# Polarshield_v2_6.net
KiCad netlist of a schematic drawn in EAGLE
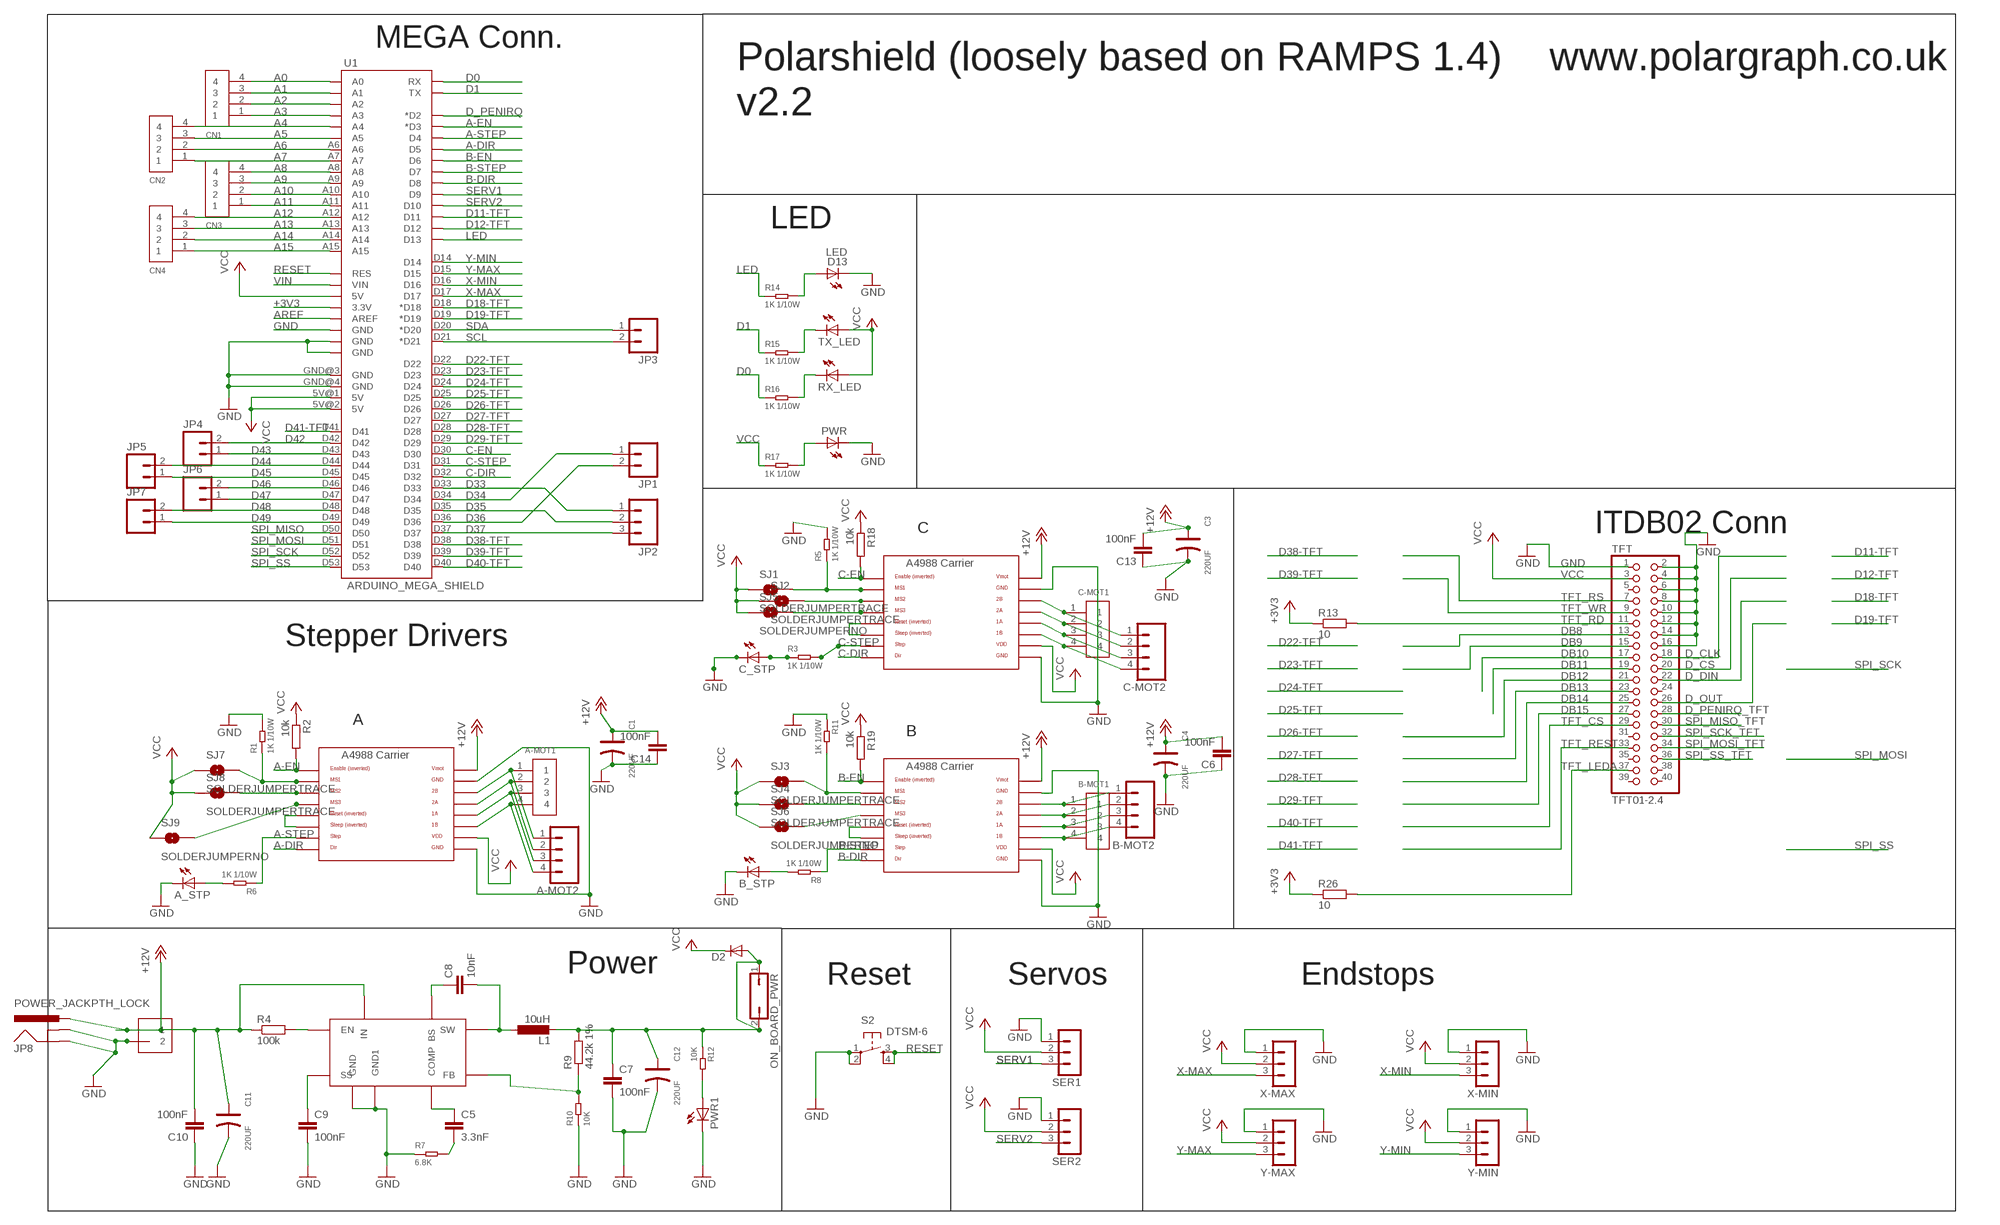
[diagram p0: schematic, sheet 1, part 1 of 2]
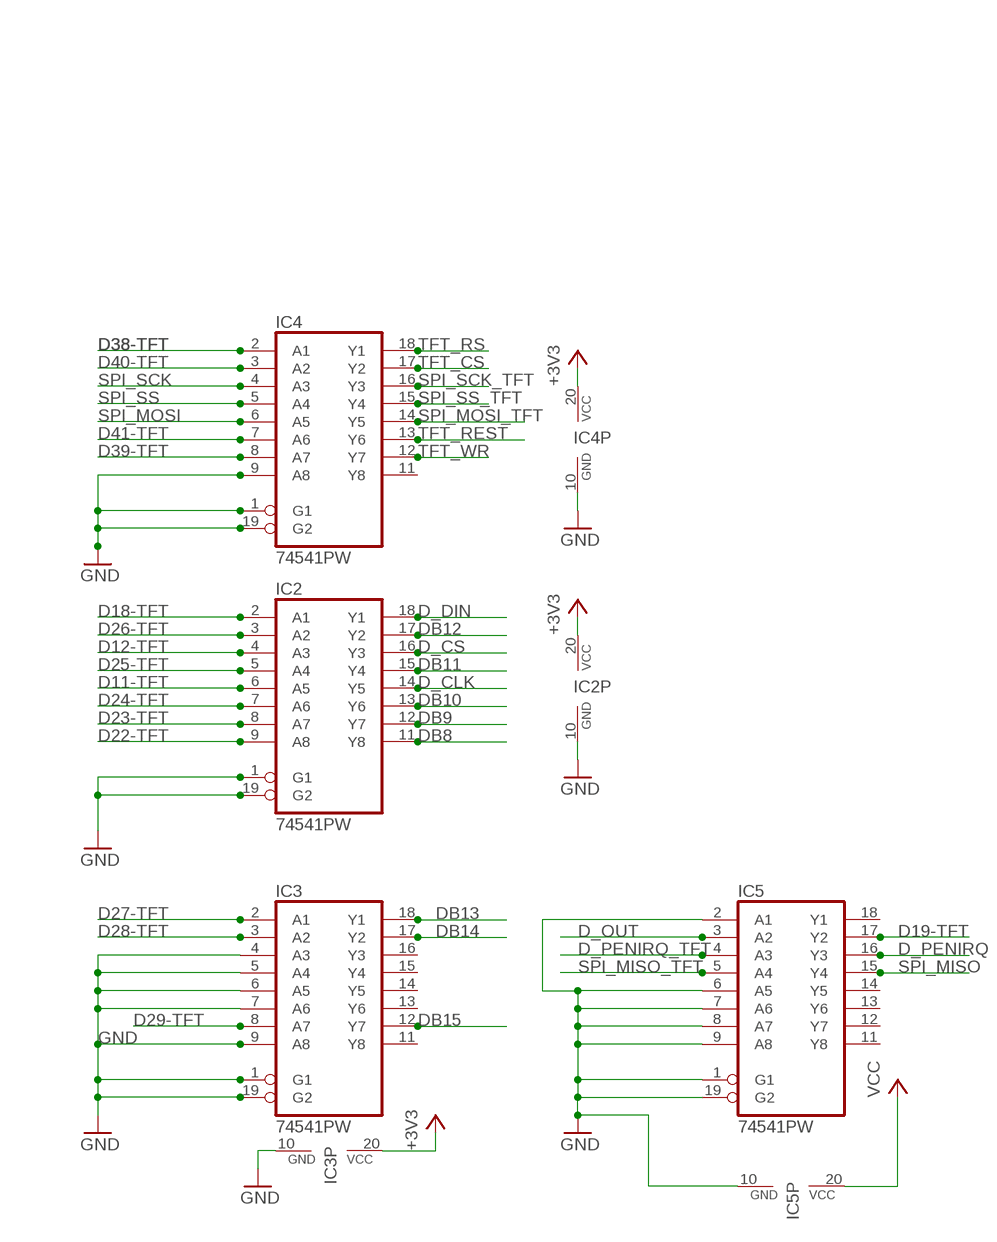
[diagram p1: schematic, sheet 1, part 2 of 2]

(export (version "E")
  (design (tool "Eeschema 10.0.6"))
  (components
    (comp (ref "A-MOT1")
      (value "1X4-BIG")
      (footprint "eagle-import:1X04-BIG")
      (libsource (lib "eagle-import") (part "adafruit_1X4-BIG"))
    )
    (comp (ref "A-MOT2")
      (value "M04SCREW")
      (footprint "eagle-import:SCREWTERMINAL-3.5MM-4")
      (libsource (lib "eagle-import") (part "M04SCREW"))
    )
    (comp (ref "A_STP")
      (value "LEDCHIP-LED0805")
      (footprint "eagle-import:CHIP-LED0805")
      (libsource (lib "eagle-import") (part "LEDCHIP-LED0805"))
    )
    (comp (ref "B-MOT1")
      (value "1X4-BIG")
      (footprint "eagle-import:1X04-BIG")
      (libsource (lib "eagle-import") (part "adafruit_1X4-BIG"))
    )
    (comp (ref "B-MOT2")
      (value "M04SCREW")
      (footprint "eagle-import:SCREWTERMINAL-3.5MM-4")
      (libsource (lib "eagle-import") (part "M04SCREW"))
    )
    (comp (ref "B_STP")
      (value "LEDCHIP-LED0805")
      (footprint "eagle-import:CHIP-LED0805")
      (libsource (lib "eagle-import") (part "LEDCHIP-LED0805"))
    )
    (comp (ref "C-MOT1")
      (value "1X4-BIG")
      (footprint "eagle-import:1X04-BIG")
      (libsource (lib "eagle-import") (part "adafruit_1X4-BIG"))
    )
    (comp (ref "C-MOT2")
      (value "M04SCREW")
      (footprint "eagle-import:SCREWTERMINAL-3.5MM-4")
      (libsource (lib "eagle-import") (part "M04SCREW"))
    )
    (comp (ref "C1")
      (value "220UF")
      (footprint "eagle-import:ELECTRO-SMD-C-6MM")
      (fields (field (name "MPN") "CS1E221M-CRE77"))
      (libsource (lib "eagle-import") (part "ALUMINUM-SMD-220UF-16V(D6.3-H7.7MM)"))
    )
    (comp (ref "C3")
      (value "220UF")
      (footprint "eagle-import:ELECTRO-SMD-C-6MM")
      (fields (field (name "MPN") "CS1E221M-CRE77"))
      (libsource (lib "eagle-import") (part "ALUMINUM-SMD-220UF-16V(D6.3-H7.7MM)"))
    )
    (comp (ref "C4")
      (value "220UF")
      (footprint "eagle-import:ELECTRO-SMD-C-6MM")
      (fields (field (name "MPN") "CS1E221M-CRE77"))
      (libsource (lib "eagle-import") (part "ALUMINUM-SMD-220UF-16V(D6.3-H7.7MM)"))
    )
    (comp (ref "C5")
      (value "3.3nF")
      (footprint "eagle-import:C0402K")
      (libsource (lib "eagle-import") (part "C-EUC0402K"))
    )
    (comp (ref "C6")
      (value "100nF")
      (footprint "eagle-import:C0402K")
      (libsource (lib "eagle-import") (part "C-EUC0402K"))
    )
    (comp (ref "C7")
      (value "100nF")
      (footprint "eagle-import:C0402K")
      (libsource (lib "eagle-import") (part "C-EUC0402K"))
    )
    (comp (ref "C8")
      (value "10nF")
      (footprint "eagle-import:C0402K")
      (libsource (lib "eagle-import") (part "C-EUC0402K"))
    )
    (comp (ref "C9")
      (value "100nF")
      (footprint "eagle-import:C0402K")
      (libsource (lib "eagle-import") (part "C-EUC0402K"))
    )
    (comp (ref "C10")
      (value "100nF")
      (footprint "eagle-import:C0402K")
      (libsource (lib "eagle-import") (part "C-EUC0402K"))
    )
    (comp (ref "C11")
      (value "220UF")
      (footprint "eagle-import:ELECTRO-SMD-C-6MM")
      (fields (field (name "MPN") "CS1E221M-CRE77"))
      (libsource (lib "eagle-import") (part "ALUMINUM-SMD-220UF-16V(D6.3-H7.7MM)"))
    )
    (comp (ref "C12")
      (value "220UF")
      (footprint "eagle-import:ELECTRO-SMD-C-6MM")
      (fields (field (name "MPN") "CS1E221M-CRE77"))
      (libsource (lib "eagle-import") (part "ALUMINUM-SMD-220UF-16V(D6.3-H7.7MM)"))
    )
    (comp (ref "C13")
      (value "100nF")
      (footprint "eagle-import:C0402K")
      (libsource (lib "eagle-import") (part "C-EUC0402K"))
    )
    (comp (ref "C14")
      (value "100nF")
      (footprint "eagle-import:C0402K")
      (libsource (lib "eagle-import") (part "C-EUC0402K"))
    )
    (comp (ref "CN1")
      (value "1X4-CLEANBIG")
      (footprint "eagle-import:1X04-CLEANBIG")
      (libsource (lib "eagle-import") (part "1X4-CLEANBIG"))
    )
    (comp (ref "CN2")
      (value "1X4-CLEANBIG")
      (footprint "eagle-import:1X04-CLEANBIG")
      (libsource (lib "eagle-import") (part "1X4-CLEANBIG"))
    )
    (comp (ref "CN3")
      (value "1X4-CLEANBIG")
      (footprint "eagle-import:1X04-CLEANBIG")
      (libsource (lib "eagle-import") (part "1X4-CLEANBIG"))
    )
    (comp (ref "CN4")
      (value "1X4-CLEANBIG")
      (footprint "eagle-import:1X04-CLEANBIG")
      (libsource (lib "eagle-import") (part "1X4-CLEANBIG"))
    )
    (comp (ref "C_STP")
      (value "LEDCHIP-LED0805")
      (footprint "eagle-import:CHIP-LED0805")
      (libsource (lib "eagle-import") (part "LEDCHIP-LED0805"))
    )
    (comp (ref "D2")
      (value "DIODE-DO214BA")
      (footprint "eagle-import:DO214BA")
      (libsource (lib "eagle-import") (part "DIODE-DO214BA"))
    )
    (comp (ref "D13")
      (value "LED")
      (footprint "eagle-import:CHIP-LED0805")
      (libsource (lib "eagle-import") (part "LEDCHIP-LED0805"))
    )
    (comp (ref "IC1")
      (value "MP2307")
      (footprint "eagle-import:SOIC8")
      (libsource (lib "eagle-import") (part "MP2307"))
    )
    (comp (ref "IC2")
      (value "74541PW")
      (footprint "eagle-import:TSSOP20")
      (libsource (lib "eagle-import") (part "74541PW"))
    )
    (comp (ref "IC3")
      (value "74541PW")
      (footprint "eagle-import:TSSOP20")
      (libsource (lib "eagle-import") (part "74541PW"))
    )
    (comp (ref "IC4")
      (value "74541PW")
      (footprint "eagle-import:TSSOP20")
      (libsource (lib "eagle-import") (part "74541PW"))
    )
    (comp (ref "IC5")
      (value "74541PW")
      (footprint "eagle-import:TSSOP20")
      (libsource (lib "eagle-import") (part "74541PW"))
    )
    (comp (ref "J1")
      (value "1X2-3.5MM")
      (footprint "eagle-import:1X2-3.5MM")
      (libsource (lib "eagle-import") (part "1X2-3.5MM"))
    )
    (comp (ref "JP1")
      (value "M021X02_NO_SILK")
      (footprint "eagle-import:1X02_NO_SILK")
      (libsource (lib "eagle-import") (part "M021X02_NO_SILK"))
    )
    (comp (ref "JP2")
      (value "M031X03_NO_SILK")
      (footprint "eagle-import:1X03_NO_SILK")
      (libsource (lib "eagle-import") (part "M031X03_NO_SILK"))
    )
    (comp (ref "JP3")
      (value "M021X02_NO_SILK")
      (footprint "eagle-import:1X02_NO_SILK")
      (libsource (lib "eagle-import") (part "M021X02_NO_SILK"))
    )
    (comp (ref "JP4")
      (value "M021X02_NO_SILK")
      (footprint "eagle-import:1X02_NO_SILK")
      (libsource (lib "eagle-import") (part "M021X02_NO_SILK"))
    )
    (comp (ref "JP5")
      (value "M021X02_NO_SILK")
      (footprint "eagle-import:1X02_NO_SILK")
      (libsource (lib "eagle-import") (part "M021X02_NO_SILK"))
    )
    (comp (ref "JP6")
      (value "M021X02_NO_SILK")
      (footprint "eagle-import:1X02_NO_SILK")
      (libsource (lib "eagle-import") (part "M021X02_NO_SILK"))
    )
    (comp (ref "JP7")
      (value "M021X02_NO_SILK")
      (footprint "eagle-import:1X02_NO_SILK")
      (libsource (lib "eagle-import") (part "M021X02_NO_SILK"))
    )
    (comp (ref "JP8")
      (value "POWER_JACKPTH_LOCK")
      (footprint "eagle-import:POWER_JACK_PTH_LOCK")
      (libsource (lib "eagle-import") (part "POWER_JACKPTH_LOCK"))
    )
    (comp (ref "L1")
      (value "10uH")
      (footprint "eagle-import:PIS2816")
      (libsource (lib "eagle-import") (part "L-EUPIS2816"))
    )
    (comp (ref "ON_BOARD_PWR")
      (value "JP1Q")
      (footprint "eagle-import:JP1")
      (libsource (lib "eagle-import") (part "JP1Q"))
    )
    (comp (ref "PWR")
      (value "LEDCHIP-LED0805")
      (footprint "eagle-import:CHIP-LED0805")
      (libsource (lib "eagle-import") (part "LEDCHIP-LED0805"))
    )
    (comp (ref "PWR1")
      (value "LEDCHIP-LED0805")
      (footprint "eagle-import:CHIP-LED0805")
      (libsource (lib "eagle-import") (part "LEDCHIP-LED0805"))
    )
    (comp (ref "R1")
      (value "1K 1/10W")
      (footprint "eagle-import:R0603")
      (fields (field (name "MPN") "RC0603JR-071KL"))
      (libsource (lib "eagle-import") (part "SMD-RES-1K-5%-1/10W(0603)"))
    )
    (comp (ref "R2")
      (value "10k")
      (footprint "eagle-import:R0402")
      (libsource (lib "eagle-import") (part "R-EU_R0402"))
    )
    (comp (ref "R3")
      (value "1K 1/10W")
      (footprint "eagle-import:R0603")
      (fields (field (name "MPN") "RC0603JR-071KL"))
      (libsource (lib "eagle-import") (part "SMD-RES-1K-5%-1/10W(0603)"))
    )
    (comp (ref "R4")
      (value "100k")
      (footprint "eagle-import:R0603")
      (libsource (lib "eagle-import") (part "R-EU_R0603"))
    )
    (comp (ref "R5")
      (value "1K 1/10W")
      (footprint "eagle-import:R0603")
      (fields (field (name "MPN") "RC0603JR-071KL"))
      (libsource (lib "eagle-import") (part "SMD-RES-1K-5%-1/10W(0603)"))
    )
    (comp (ref "R6")
      (value "1K 1/10W")
      (footprint "eagle-import:R0603")
      (fields (field (name "MPN") "RC0603JR-071KL"))
      (libsource (lib "eagle-import") (part "SMD-RES-1K-5%-1/10W(0603)"))
    )
    (comp (ref "R7")
      (value "6.8K")
      (footprint "eagle-import:R0603")
      (fields (field (name "MPN") "RC0805JR-07220KL"))
      (libsource (lib "eagle-import") (part "SMD-RES-6.8K-1%-1/10W(0603)"))
    )
    (comp (ref "R8")
      (value "1K 1/10W")
      (footprint "eagle-import:R0603")
      (fields (field (name "MPN") "RC0603JR-071KL"))
      (libsource (lib "eagle-import") (part "SMD-RES-1K-5%-1/10W(0603)"))
    )
    (comp (ref "R9")
      (value "44.2k 1%")
      (footprint "eagle-import:R0603")
      (libsource (lib "eagle-import") (part "R-EU_R0603"))
    )
    (comp (ref "R10")
      (value "10K")
      (footprint "eagle-import:R0805")
      (fields (field (name "MPN") "RC0805FR-0710KL"))
      (libsource (lib "eagle-import") (part "SMD-RES-10K-1%-1/8W(0805)"))
    )
    (comp (ref "R11")
      (value "1K 1/10W")
      (footprint "eagle-import:R0603")
      (fields (field (name "MPN") "RC0603JR-071KL"))
      (libsource (lib "eagle-import") (part "SMD-RES-1K-5%-1/10W(0603)"))
    )
    (comp (ref "R12")
      (value "10K")
      (footprint "eagle-import:R0603")
      (fields (field (name "MPN") "RC0603FR-0710KL"))
      (libsource (lib "eagle-import") (part "SMD-RES-10K-1%-1/10W(0603)"))
    )
    (comp (ref "R13")
      (value "10")
      (footprint "eagle-import:R0603")
      (libsource (lib "eagle-import") (part "R-EU_R0603"))
    )
    (comp (ref "R14")
      (value "1K 1/10W")
      (footprint "eagle-import:R0603")
      (fields (field (name "MPN") "RC0603JR-071KL"))
      (libsource (lib "eagle-import") (part "SMD-RES-1K-5%-1/10W(0603)"))
    )
    (comp (ref "R15")
      (value "1K 1/10W")
      (footprint "eagle-import:R0603")
      (fields (field (name "MPN") "RC0603JR-071KL"))
      (libsource (lib "eagle-import") (part "SMD-RES-1K-5%-1/10W(0603)"))
    )
    (comp (ref "R16")
      (value "1K 1/10W")
      (footprint "eagle-import:R0603")
      (fields (field (name "MPN") "RC0603JR-071KL"))
      (libsource (lib "eagle-import") (part "SMD-RES-1K-5%-1/10W(0603)"))
    )
    (comp (ref "R17")
      (value "1K 1/10W")
      (footprint "eagle-import:R0603")
      (fields (field (name "MPN") "RC0603JR-071KL"))
      (libsource (lib "eagle-import") (part "SMD-RES-1K-5%-1/10W(0603)"))
    )
    (comp (ref "R18")
      (value "10k")
      (footprint "eagle-import:R0402")
      (libsource (lib "eagle-import") (part "R-EU_R0402"))
    )
    (comp (ref "R19")
      (value "10k")
      (footprint "eagle-import:R0402")
      (libsource (lib "eagle-import") (part "R-EU_R0402"))
    )
    (comp (ref "R26")
      (value "10")
      (footprint "eagle-import:R0603")
      (libsource (lib "eagle-import") (part "R-EU_R0603"))
    )
    (comp (ref "RX_LED")
      (value "LEDCHIP-LED0805")
      (footprint "eagle-import:CHIP-LED0805")
      (libsource (lib "eagle-import") (part "LEDCHIP-LED0805"))
    )
    (comp (ref "S2")
      (value "DTSM-6")
      (footprint "eagle-import:DTSM-6")
      (libsource (lib "eagle-import") (part "DTSM-6"))
    )
    (comp (ref "SER1")
      (value "3PIN-HEADER")
      (footprint "eagle-import:3PIN-HEADER")
      (libsource (lib "eagle-import") (part "3PIN-HEADER"))
    )
    (comp (ref "SER2")
      (value "3PIN-HEADER")
      (footprint "eagle-import:3PIN-HEADER")
      (libsource (lib "eagle-import") (part "3PIN-HEADER"))
    )
    (comp (ref "SJ1")
      (value "SOLDERJUMPERTRACE")
      (footprint "eagle-import:SJ_2S-TRACE")
      (libsource (lib "eagle-import") (part "SOLDERJUMPERTRACE"))
    )
    (comp (ref "SJ2")
      (value "SOLDERJUMPERTRACE")
      (footprint "eagle-import:SJ_2S-TRACE")
      (libsource (lib "eagle-import") (part "SOLDERJUMPERTRACE"))
    )
    (comp (ref "SJ3")
      (value "SOLDERJUMPERTRACE")
      (footprint "eagle-import:SJ_2S-TRACE")
      (libsource (lib "eagle-import") (part "SOLDERJUMPERTRACE"))
    )
    (comp (ref "SJ4")
      (value "SOLDERJUMPERTRACE")
      (footprint "eagle-import:SJ_2S-TRACE")
      (libsource (lib "eagle-import") (part "SOLDERJUMPERTRACE"))
    )
    (comp (ref "SJ5")
      (value "SOLDERJUMPERNO")
      (footprint "eagle-import:SJ_2S-NO")
      (libsource (lib "eagle-import") (part "SOLDERJUMPERNO"))
    )
    (comp (ref "SJ6")
      (value "SOLDERJUMPERNO")
      (footprint "eagle-import:SJ_2S-NO")
      (libsource (lib "eagle-import") (part "SOLDERJUMPERNO"))
    )
    (comp (ref "SJ7")
      (value "SOLDERJUMPERTRACE")
      (footprint "eagle-import:SJ_2S-TRACE")
      (libsource (lib "eagle-import") (part "SOLDERJUMPERTRACE"))
    )
    (comp (ref "SJ8")
      (value "SOLDERJUMPERTRACE")
      (footprint "eagle-import:SJ_2S-TRACE")
      (libsource (lib "eagle-import") (part "SOLDERJUMPERTRACE"))
    )
    (comp (ref "SJ9")
      (value "SOLDERJUMPERNO")
      (footprint "eagle-import:SJ_2S-NO")
      (libsource (lib "eagle-import") (part "SOLDERJUMPERNO"))
    )
    (comp (ref "TFT")
      (value "TFT01-2.4")
      (footprint "eagle-import:TFT01-2.4")
      (libsource (lib "eagle-import") (part "TFT01-2.4"))
    )
    (comp (ref "TX_LED")
      (value "LEDCHIP-LED0805")
      (footprint "eagle-import:CHIP-LED0805")
      (libsource (lib "eagle-import") (part "LEDCHIP-LED0805"))
    )
    (comp (ref "U$1")
      (value "A4988BREAKOUT")
      (footprint "eagle-import:A4988BREAKOUT")
      (libsource (lib "eagle-import") (part "A4988BREAKOUT"))
    )
    (comp (ref "U$6")
      (value "A4988BREAKOUT")
      (footprint "eagle-import:A4988BREAKOUT")
      (libsource (lib "eagle-import") (part "A4988BREAKOUT"))
    )
    (comp (ref "U$7")
      (value "A4988BREAKOUT")
      (footprint "eagle-import:A4988BREAKOUT")
      (libsource (lib "eagle-import") (part "A4988BREAKOUT"))
    )
    (comp (ref "U1")
      (value "ARDUINO_MEGA_SHIELD")
      (footprint "eagle-import:ARDUINO_MEGA_SHIELD")
      (libsource (lib "eagle-import") (part "ARDUINO_MEGA_SHIELD"))
    )
    (comp (ref "X-MAX")
      (value "3PIN-HEADER")
      (footprint "eagle-import:3PIN-HEADER")
      (libsource (lib "eagle-import") (part "3PIN-HEADER"))
    )
    (comp (ref "X-MIN")
      (value "3PIN-HEADER")
      (footprint "eagle-import:3PIN-HEADER")
      (libsource (lib "eagle-import") (part "3PIN-HEADER"))
    )
    (comp (ref "Y-MAX")
      (value "3PIN-HEADER")
      (footprint "eagle-import:3PIN-HEADER")
      (libsource (lib "eagle-import") (part "3PIN-HEADER"))
    )
    (comp (ref "Y-MIN")
      (value "3PIN-HEADER")
      (footprint "eagle-import:3PIN-HEADER")
      (libsource (lib "eagle-import") (part "3PIN-HEADER"))
    )
  )
  (nets
    (net (code "1") (name "+3V3") (class "Default")
      (node (ref "IC2") (pin "20") (pinfunction "VCC_20") (pintype "power_in"))
      (node (ref "IC3") (pin "20") (pinfunction "VCC_20") (pintype "power_in"))
      (node (ref "IC4") (pin "20") (pinfunction "VCC_20") (pintype "power_in"))
      (node (ref "R13") (pin "1") (pinfunction "1_1") (pintype "passive"))
      (node (ref "R26") (pin "1") (pinfunction "1_1") (pintype "passive"))
      (node (ref "U1") (pin "3.3V") (pinfunction "3.3V_3.3V") (pintype "bidirectional"))
    )
    (net (code "2") (name "+12V") (class "Default")
      (node (ref "C1") (pin "+") (pinfunction "+_+") (pintype "passive"))
      (node (ref "C10") (pin "2") (pinfunction "2_2") (pintype "passive"))
      (node (ref "C11") (pin "+") (pinfunction "+_+") (pintype "passive"))
      (node (ref "C13") (pin "2") (pinfunction "2_2") (pintype "passive"))
      (node (ref "C14") (pin "2") (pinfunction "2_2") (pintype "passive"))
      (node (ref "C3") (pin "+") (pinfunction "+_+") (pintype "passive"))
      (node (ref "C4") (pin "+") (pinfunction "+_+") (pintype "passive"))
      (node (ref "C6") (pin "2") (pinfunction "2_2") (pintype "passive"))
      (node (ref "IC1") (pin "IN") (pinfunction "IN_IN") (pintype "bidirectional"))
      (node (ref "J1") (pin "1") (pinfunction "1_1") (pintype "passive"))
      (node (ref "JP8") (pin "PWR") (pinfunction "PWR_PWR") (pintype "bidirectional"))
      (node (ref "R4") (pin "1") (pinfunction "1_1") (pintype "passive"))
      (node (ref "U$1") (pin "VMOT") (pinfunction "VMOT_VMOT") (pintype "power_in"))
      (node (ref "U$6") (pin "VMOT") (pinfunction "VMOT_VMOT") (pintype "power_in"))
      (node (ref "U$7") (pin "VMOT") (pinfunction "VMOT_VMOT") (pintype "power_in"))
    )
    (net (code "3") (name "/A-DIR") (class "Default")
      (node (ref "U$1") (pin "DIR") (pinfunction "DIR_DIR") (pintype "input"))
      (node (ref "U1") (pin "D5") (pinfunction "D5_D5") (pintype "bidirectional"))
    )
    (net (code "4") (name "/A-EN") (class "Default")
      (node (ref "R2") (pin "2") (pinfunction "2_2") (pintype "passive"))
      (node (ref "U$1") (pin "EN") (pinfunction "EN_EN") (pintype "input"))
      (node (ref "U1") (pin "D3") (pinfunction "*D3_D3") (pintype "bidirectional"))
    )
    (net (code "5") (name "/A-STEP") (class "Default")
      (node (ref "R6") (pin "1") (pinfunction "1_1") (pintype "passive"))
      (node (ref "U$1") (pin "STEP") (pinfunction "STEP_STEP") (pintype "input"))
      (node (ref "U1") (pin "D4") (pinfunction "D4_D4") (pintype "bidirectional"))
    )
    (net (code "6") (name "/A0") (class "Default")
      (node (ref "CN1") (pin "4") (pinfunction "4_4") (pintype "bidirectional"))
      (node (ref "U1") (pin "A0") (pinfunction "A0_A0") (pintype "bidirectional"))
    )
    (net (code "7") (name "/A1") (class "Default")
      (node (ref "CN1") (pin "3") (pinfunction "3_3") (pintype "bidirectional"))
      (node (ref "U1") (pin "A1") (pinfunction "A1_A1") (pintype "bidirectional"))
    )
    (net (code "8") (name "/A2") (class "Default")
      (node (ref "CN1") (pin "2") (pinfunction "2_2") (pintype "bidirectional"))
      (node (ref "U1") (pin "A2") (pinfunction "A2_A2") (pintype "bidirectional"))
    )
    (net (code "9") (name "/A3") (class "Default")
      (node (ref "CN1") (pin "1") (pinfunction "1_1") (pintype "bidirectional"))
      (node (ref "U1") (pin "A3") (pinfunction "A3_A3") (pintype "bidirectional"))
    )
    (net (code "10") (name "/A4") (class "Default")
      (node (ref "CN2") (pin "4") (pinfunction "4_4") (pintype "bidirectional"))
      (node (ref "U1") (pin "A4") (pinfunction "A4_A4") (pintype "bidirectional"))
    )
    (net (code "11") (name "/A5") (class "Default")
      (node (ref "CN2") (pin "3") (pinfunction "3_3") (pintype "bidirectional"))
      (node (ref "U1") (pin "A5") (pinfunction "A5_A5") (pintype "bidirectional"))
    )
    (net (code "12") (name "/A6") (class "Default")
      (node (ref "CN2") (pin "2") (pinfunction "2_2") (pintype "bidirectional"))
      (node (ref "U1") (pin "A6") (pinfunction "A6_A6") (pintype "bidirectional"))
    )
    (net (code "13") (name "/A7") (class "Default")
      (node (ref "CN2") (pin "1") (pinfunction "1_1") (pintype "bidirectional"))
      (node (ref "U1") (pin "A7") (pinfunction "A7_A7") (pintype "bidirectional"))
    )
    (net (code "14") (name "/A8") (class "Default")
      (node (ref "CN3") (pin "4") (pinfunction "4_4") (pintype "bidirectional"))
      (node (ref "U1") (pin "A8") (pinfunction "A8_A8") (pintype "bidirectional"))
    )
    (net (code "15") (name "/A9") (class "Default")
      (node (ref "CN3") (pin "3") (pinfunction "3_3") (pintype "bidirectional"))
      (node (ref "U1") (pin "A9") (pinfunction "A9_A9") (pintype "bidirectional"))
    )
    (net (code "16") (name "/A10") (class "Default")
      (node (ref "CN3") (pin "2") (pinfunction "2_2") (pintype "bidirectional"))
      (node (ref "U1") (pin "A10") (pinfunction "A10_A10") (pintype "bidirectional"))
    )
    (net (code "17") (name "/A11") (class "Default")
      (node (ref "CN3") (pin "1") (pinfunction "1_1") (pintype "bidirectional"))
      (node (ref "U1") (pin "A11") (pinfunction "A11_A11") (pintype "bidirectional"))
    )
    (net (code "18") (name "/A12") (class "Default")
      (node (ref "CN4") (pin "4") (pinfunction "4_4") (pintype "bidirectional"))
      (node (ref "U1") (pin "A12") (pinfunction "A12_A12") (pintype "bidirectional"))
    )
    (net (code "19") (name "/A13") (class "Default")
      (node (ref "CN4") (pin "3") (pinfunction "3_3") (pintype "bidirectional"))
      (node (ref "U1") (pin "A13") (pinfunction "A13_A13") (pintype "bidirectional"))
    )
    (net (code "20") (name "/A14") (class "Default")
      (node (ref "CN4") (pin "2") (pinfunction "2_2") (pintype "bidirectional"))
      (node (ref "U1") (pin "A14") (pinfunction "A14_A14") (pintype "bidirectional"))
    )
    (net (code "21") (name "/A15") (class "Default")
      (node (ref "CN4") (pin "1") (pinfunction "1_1") (pintype "bidirectional"))
      (node (ref "U1") (pin "A15") (pinfunction "A15_A15") (pintype "bidirectional"))
    )
    (net (code "22") (name "/AREF") (class "Default")
      (node (ref "U1") (pin "AREF") (pinfunction "AREF_AREF") (pintype "bidirectional"))
    )
    (net (code "23") (name "/B-DIR") (class "Default")
      (node (ref "U$7") (pin "DIR") (pinfunction "DIR_DIR") (pintype "input"))
      (node (ref "U1") (pin "D8") (pinfunction "D8_D8") (pintype "bidirectional"))
    )
    (net (code "24") (name "/B-EN") (class "Default")
      (node (ref "R19") (pin "2") (pinfunction "2_2") (pintype "passive"))
      (node (ref "U$7") (pin "EN") (pinfunction "EN_EN") (pintype "input"))
      (node (ref "U1") (pin "D6") (pinfunction "D6_D6") (pintype "bidirectional"))
    )
    (net (code "25") (name "/B-STEP") (class "Default")
      (node (ref "R8") (pin "1") (pinfunction "1_1") (pintype "passive"))
      (node (ref "U$7") (pin "STEP") (pinfunction "STEP_STEP") (pintype "input"))
      (node (ref "U1") (pin "D7") (pinfunction "D7_D7") (pintype "bidirectional"))
    )
    (net (code "26") (name "/C-DIR") (class "Default")
      (node (ref "U$6") (pin "DIR") (pinfunction "DIR_DIR") (pintype "input"))
      (node (ref "U1") (pin "D32") (pinfunction "D32_D32") (pintype "bidirectional"))
    )
    (net (code "27") (name "/C-EN") (class "Default")
      (node (ref "R18") (pin "2") (pinfunction "2_2") (pintype "passive"))
      (node (ref "U$6") (pin "EN") (pinfunction "EN_EN") (pintype "input"))
      (node (ref "U1") (pin "D30") (pinfunction "D30_D30") (pintype "bidirectional"))
    )
    (net (code "28") (name "/C-STEP") (class "Default")
      (node (ref "R3") (pin "2") (pinfunction "2_2") (pintype "passive"))
      (node (ref "U$6") (pin "STEP") (pinfunction "STEP_STEP") (pintype "input"))
      (node (ref "U1") (pin "D31") (pinfunction "D31_D31") (pintype "bidirectional"))
    )
    (net (code "29") (name "/D0") (class "Default")
      (node (ref "R16") (pin "1") (pinfunction "1_1") (pintype "passive"))
      (node (ref "U1") (pin "RX") (pinfunction "RX_RX") (pintype "bidirectional"))
    )
    (net (code "30") (name "/D1") (class "Default")
      (node (ref "R15") (pin "1") (pinfunction "1_1") (pintype "passive"))
      (node (ref "U1") (pin "TX") (pinfunction "TX_TX") (pintype "bidirectional"))
    )
    (net (code "31") (name "/D11-TFT") (class "Default")
      (node (ref "IC2") (pin "6") (pinfunction "A5_6") (pintype "input"))
      (node (ref "U1") (pin "D11") (pinfunction "D11_D11") (pintype "bidirectional"))
    )
    (net (code "32") (name "/D12-TFT") (class "Default")
      (node (ref "IC2") (pin "4") (pinfunction "A3_4") (pintype "input"))
      (node (ref "U1") (pin "D12") (pinfunction "D12_D12") (pintype "bidirectional"))
    )
    (net (code "33") (name "/D18-TFT") (class "Default")
      (node (ref "IC2") (pin "2") (pinfunction "A1_2") (pintype "input"))
      (node (ref "U1") (pin "D18") (pinfunction "*D18_D18") (pintype "bidirectional"))
    )
    (net (code "34") (name "/D19-TFT") (class "Default")
      (node (ref "IC5") (pin "17") (pinfunction "Y2_17") (pintype "tri_state"))
      (node (ref "U1") (pin "D19") (pinfunction "*D19_D19") (pintype "bidirectional"))
    )
    (net (code "35") (name "/D22-TFT") (class "Default")
      (node (ref "IC2") (pin "9") (pinfunction "A8_9") (pintype "input"))
      (node (ref "U1") (pin "D22") (pinfunction "D22_D22") (pintype "bidirectional"))
    )
    (net (code "36") (name "/D23-TFT") (class "Default")
      (node (ref "IC2") (pin "8") (pinfunction "A7_8") (pintype "input"))
      (node (ref "U1") (pin "D23") (pinfunction "D23_D23") (pintype "bidirectional"))
    )
    (net (code "37") (name "/D24-TFT") (class "Default")
      (node (ref "IC2") (pin "7") (pinfunction "A6_7") (pintype "input"))
      (node (ref "U1") (pin "D24") (pinfunction "D24_D24") (pintype "bidirectional"))
    )
    (net (code "38") (name "/D25-TFT") (class "Default")
      (node (ref "IC2") (pin "5") (pinfunction "A4_5") (pintype "input"))
      (node (ref "U1") (pin "D25") (pinfunction "D25_D25") (pintype "bidirectional"))
    )
    (net (code "39") (name "/D26-TFT") (class "Default")
      (node (ref "IC2") (pin "3") (pinfunction "A2_3") (pintype "input"))
      (node (ref "U1") (pin "D26") (pinfunction "D26_D26") (pintype "bidirectional"))
    )
    (net (code "40") (name "/D27-TFT") (class "Default")
      (node (ref "IC3") (pin "2") (pinfunction "A1_2") (pintype "input"))
      (node (ref "U1") (pin "D27") (pinfunction "D27_D27") (pintype "bidirectional"))
    )
    (net (code "41") (name "/D28-TFT") (class "Default")
      (node (ref "IC3") (pin "3") (pinfunction "A2_3") (pintype "input"))
      (node (ref "U1") (pin "D28") (pinfunction "D28_D28") (pintype "bidirectional"))
    )
    (net (code "42") (name "/D29-TFT") (class "Default")
      (node (ref "IC3") (pin "8") (pinfunction "A7_8") (pintype "input"))
      (node (ref "U1") (pin "D29") (pinfunction "D29_D29") (pintype "bidirectional"))
    )
    (net (code "43") (name "/D33") (class "Default")
      (node (ref "JP2") (pin "1") (pinfunction "1_1") (pintype "passive"))
      (node (ref "U1") (pin "D33") (pinfunction "D33_D33") (pintype "bidirectional"))
    )
    (net (code "44") (name "/D34") (class "Default")
      (node (ref "JP1") (pin "1") (pinfunction "1_1") (pintype "passive"))
      (node (ref "U1") (pin "D34") (pinfunction "D34_D34") (pintype "bidirectional"))
    )
    (net (code "45") (name "/D35") (class "Default")
      (node (ref "JP2") (pin "2") (pinfunction "2_2") (pintype "passive"))
      (node (ref "U1") (pin "D35") (pinfunction "D35_D35") (pintype "bidirectional"))
    )
    (net (code "46") (name "/D36") (class "Default")
      (node (ref "JP1") (pin "2") (pinfunction "2_2") (pintype "passive"))
      (node (ref "U1") (pin "D36") (pinfunction "D36_D36") (pintype "bidirectional"))
    )
    (net (code "47") (name "/D37") (class "Default")
      (node (ref "JP2") (pin "3") (pinfunction "3_3") (pintype "passive"))
      (node (ref "U1") (pin "D37") (pinfunction "D37_D37") (pintype "bidirectional"))
    )
    (net (code "48") (name "/D38-TFT") (class "Default")
      (node (ref "IC4") (pin "2") (pinfunction "A1_2") (pintype "input"))
      (node (ref "U1") (pin "D38") (pinfunction "D38_D38") (pintype "bidirectional"))
    )
    (net (code "49") (name "/D39-TFT") (class "Default")
      (node (ref "IC4") (pin "8") (pinfunction "A7_8") (pintype "input"))
      (node (ref "U1") (pin "D39") (pinfunction "D39_D39") (pintype "bidirectional"))
    )
    (net (code "50") (name "/D40-TFT") (class "Default")
      (node (ref "IC4") (pin "3") (pinfunction "A2_3") (pintype "input"))
      (node (ref "U1") (pin "D40") (pinfunction "D40_D40") (pintype "bidirectional"))
    )
    (net (code "51") (name "/D41-TFT") (class "Default")
      (node (ref "IC4") (pin "7") (pinfunction "A6_7") (pintype "input"))
      (node (ref "U1") (pin "D41") (pinfunction "D41_D41") (pintype "bidirectional"))
    )
    (net (code "52") (name "/D42") (class "Default")
      (node (ref "JP4") (pin "2") (pinfunction "2_2") (pintype "passive"))
      (node (ref "U1") (pin "D42") (pinfunction "D42_D42") (pintype "bidirectional"))
    )
    (net (code "53") (name "/D43") (class "Default")
      (node (ref "JP4") (pin "1") (pinfunction "1_1") (pintype "passive"))
      (node (ref "U1") (pin "D43") (pinfunction "D43_D43") (pintype "bidirectional"))
    )
    (net (code "54") (name "/D44") (class "Default")
      (node (ref "JP5") (pin "2") (pinfunction "2_2") (pintype "passive"))
      (node (ref "U1") (pin "D44") (pinfunction "D44_D44") (pintype "bidirectional"))
    )
    (net (code "55") (name "/D45") (class "Default")
      (node (ref "JP5") (pin "1") (pinfunction "1_1") (pintype "passive"))
      (node (ref "U1") (pin "D45") (pinfunction "D45_D45") (pintype "bidirectional"))
    )
    (net (code "56") (name "/D46") (class "Default")
      (node (ref "JP6") (pin "2") (pinfunction "2_2") (pintype "passive"))
      (node (ref "U1") (pin "D46") (pinfunction "D46_D46") (pintype "bidirectional"))
    )
    (net (code "57") (name "/D47") (class "Default")
      (node (ref "JP6") (pin "1") (pinfunction "1_1") (pintype "passive"))
      (node (ref "U1") (pin "D47") (pinfunction "D47_D47") (pintype "bidirectional"))
    )
    (net (code "58") (name "/D48") (class "Default")
      (node (ref "JP7") (pin "2") (pinfunction "2_2") (pintype "passive"))
      (node (ref "U1") (pin "D48") (pinfunction "D48_D48") (pintype "bidirectional"))
    )
    (net (code "59") (name "/D49") (class "Default")
      (node (ref "JP7") (pin "1") (pinfunction "1_1") (pintype "passive"))
      (node (ref "U1") (pin "D49") (pinfunction "D49_D49") (pintype "bidirectional"))
    )
    (net (code "60") (name "/DB8") (class "Default")
      (node (ref "IC2") (pin "11") (pinfunction "Y8_11") (pintype "tri_state"))
      (node (ref "TFT") (pin "13") (pinfunction "13_13") (pintype "passive"))
    )
    (net (code "61") (name "/DB9") (class "Default")
      (node (ref "IC2") (pin "12") (pinfunction "Y7_12") (pintype "tri_state"))
      (node (ref "TFT") (pin "15") (pinfunction "15_15") (pintype "passive"))
    )
    (net (code "62") (name "/DB10") (class "Default")
      (node (ref "IC2") (pin "13") (pinfunction "Y6_13") (pintype "tri_state"))
      (node (ref "TFT") (pin "17") (pinfunction "17_17") (pintype "passive"))
    )
    (net (code "63") (name "/DB11") (class "Default")
      (node (ref "IC2") (pin "15") (pinfunction "Y4_15") (pintype "tri_state"))
      (node (ref "TFT") (pin "19") (pinfunction "19_19") (pintype "passive"))
    )
    (net (code "64") (name "/DB12") (class "Default")
      (node (ref "IC2") (pin "17") (pinfunction "Y2_17") (pintype "tri_state"))
      (node (ref "TFT") (pin "21") (pinfunction "21_21") (pintype "passive"))
    )
    (net (code "65") (name "/DB13") (class "Default")
      (node (ref "IC3") (pin "18") (pinfunction "Y1_18") (pintype "tri_state"))
      (node (ref "TFT") (pin "23") (pinfunction "23_23") (pintype "passive"))
    )
    (net (code "66") (name "/DB14") (class "Default")
      (node (ref "IC3") (pin "17") (pinfunction "Y2_17") (pintype "tri_state"))
      (node (ref "TFT") (pin "25") (pinfunction "25_25") (pintype "passive"))
    )
    (net (code "67") (name "/DB15") (class "Default")
      (node (ref "IC3") (pin "12") (pinfunction "Y7_12") (pintype "tri_state"))
      (node (ref "TFT") (pin "27") (pinfunction "27_27") (pintype "passive"))
    )
    (net (code "68") (name "/D_CLK") (class "Default")
      (node (ref "IC2") (pin "14") (pinfunction "Y5_14") (pintype "tri_state"))
      (node (ref "TFT") (pin "18") (pinfunction "18_18") (pintype "passive"))
    )
    (net (code "69") (name "/D_CS") (class "Default")
      (node (ref "IC2") (pin "16") (pinfunction "Y3_16") (pintype "tri_state"))
      (node (ref "TFT") (pin "20") (pinfunction "20_20") (pintype "passive"))
    )
    (net (code "70") (name "/D_DIN") (class "Default")
      (node (ref "IC2") (pin "18") (pinfunction "Y1_18") (pintype "tri_state"))
      (node (ref "TFT") (pin "22") (pinfunction "22_22") (pintype "passive"))
    )
    (net (code "71") (name "/D_OUT") (class "Default")
      (node (ref "IC5") (pin "3") (pinfunction "A2_3") (pintype "input"))
      (node (ref "TFT") (pin "26") (pinfunction "26_26") (pintype "passive"))
    )
    (net (code "72") (name "/D_PENIRQ") (class "Default")
      (node (ref "IC5") (pin "16") (pinfunction "Y3_16") (pintype "tri_state"))
      (node (ref "U1") (pin "D2") (pinfunction "*D2_D2") (pintype "bidirectional"))
    )
    (net (code "73") (name "/D_PENIRQ_TFT") (class "Default")
      (node (ref "IC5") (pin "4") (pinfunction "A3_4") (pintype "input"))
      (node (ref "TFT") (pin "28") (pinfunction "28_28") (pintype "passive"))
    )
    (net (code "74") (name "/LED") (class "Default")
      (node (ref "R14") (pin "1") (pinfunction "1_1") (pintype "passive"))
      (node (ref "U1") (pin "D13") (pinfunction "D13_D13") (pintype "bidirectional"))
    )
    (net (code "75") (name "/RESET") (class "Default")
      (node (ref "S2") (pin "3") (pinfunction "3_3") (pintype "passive"))
      (node (ref "S2") (pin "4") (pinfunction "4_4") (pintype "passive"))
      (node (ref "U1") (pin "RES") (pinfunction "RES_RES") (pintype "bidirectional"))
    )
    (net (code "76") (name "/SCL") (class "Default")
      (node (ref "JP3") (pin "2") (pinfunction "2_2") (pintype "passive"))
      (node (ref "U1") (pin "D21") (pinfunction "*D21_D21") (pintype "bidirectional"))
    )
    (net (code "77") (name "/SDA") (class "Default")
      (node (ref "JP3") (pin "1") (pinfunction "1_1") (pintype "passive"))
      (node (ref "U1") (pin "D20") (pinfunction "*D20_D20") (pintype "bidirectional"))
    )
    (net (code "78") (name "/SERV1") (class "Default")
      (node (ref "SER1") (pin "3") (pinfunction "3_3") (pintype "passive"))
      (node (ref "U1") (pin "D9") (pinfunction "D9_D9") (pintype "bidirectional"))
    )
    (net (code "79") (name "/SERV2") (class "Default")
      (node (ref "SER2") (pin "3") (pinfunction "3_3") (pintype "passive"))
      (node (ref "U1") (pin "D10") (pinfunction "D10_D10") (pintype "bidirectional"))
    )
    (net (code "80") (name "/SPI_MISO") (class "Default")
      (node (ref "IC5") (pin "15") (pinfunction "Y4_15") (pintype "tri_state"))
      (node (ref "U1") (pin "D50") (pinfunction "D50_D50") (pintype "bidirectional"))
    )
    (net (code "81") (name "/SPI_MISO_TFT") (class "Default")
      (node (ref "IC5") (pin "5") (pinfunction "A4_5") (pintype "input"))
      (node (ref "TFT") (pin "30") (pinfunction "30_30") (pintype "passive"))
    )
    (net (code "82") (name "/SPI_MOSI") (class "Default")
      (node (ref "IC4") (pin "6") (pinfunction "A5_6") (pintype "input"))
      (node (ref "U1") (pin "D51") (pinfunction "D51_D51") (pintype "bidirectional"))
    )
    (net (code "83") (name "/SPI_MOSI_TFT") (class "Default")
      (node (ref "IC4") (pin "14") (pinfunction "Y5_14") (pintype "tri_state"))
      (node (ref "TFT") (pin "34") (pinfunction "34_34") (pintype "passive"))
    )
    (net (code "84") (name "/SPI_SCK") (class "Default")
      (node (ref "IC4") (pin "4") (pinfunction "A3_4") (pintype "input"))
      (node (ref "U1") (pin "D52") (pinfunction "D52_D52") (pintype "bidirectional"))
    )
    (net (code "85") (name "/SPI_SCK_TFT") (class "Default")
      (node (ref "IC4") (pin "16") (pinfunction "Y3_16") (pintype "tri_state"))
      (node (ref "TFT") (pin "32") (pinfunction "32_32") (pintype "passive"))
    )
    (net (code "86") (name "/SPI_SS") (class "Default")
      (node (ref "IC4") (pin "5") (pinfunction "A4_5") (pintype "input"))
      (node (ref "U1") (pin "D53") (pinfunction "D53_D53") (pintype "bidirectional"))
    )
    (net (code "87") (name "/SPI_SS_TFT") (class "Default")
      (node (ref "IC4") (pin "15") (pinfunction "Y4_15") (pintype "tri_state"))
      (node (ref "TFT") (pin "36") (pinfunction "36_36") (pintype "passive"))
    )
    (net (code "88") (name "/TFT_CS") (class "Default")
      (node (ref "IC4") (pin "17") (pinfunction "Y2_17") (pintype "tri_state"))
      (node (ref "TFT") (pin "29") (pinfunction "29_29") (pintype "passive"))
    )
    (net (code "89") (name "/TFT_LEDA") (class "Default")
      (node (ref "R26") (pin "2") (pinfunction "2_2") (pintype "passive"))
      (node (ref "TFT") (pin "37") (pinfunction "37_37") (pintype "passive"))
    )
    (net (code "90") (name "/TFT_RD") (class "Default")
      (node (ref "R13") (pin "2") (pinfunction "2_2") (pintype "passive"))
      (node (ref "TFT") (pin "11") (pinfunction "11_11") (pintype "passive"))
    )
    (net (code "91") (name "/TFT_REST") (class "Default")
      (node (ref "IC4") (pin "13") (pinfunction "Y6_13") (pintype "tri_state"))
      (node (ref "TFT") (pin "33") (pinfunction "33_33") (pintype "passive"))
    )
    (net (code "92") (name "/TFT_RS") (class "Default")
      (node (ref "IC4") (pin "18") (pinfunction "Y1_18") (pintype "tri_state"))
      (node (ref "TFT") (pin "7") (pinfunction "7_7") (pintype "passive"))
    )
    (net (code "93") (name "/TFT_WR") (class "Default")
      (node (ref "IC4") (pin "12") (pinfunction "Y7_12") (pintype "tri_state"))
      (node (ref "TFT") (pin "9") (pinfunction "9_9") (pintype "passive"))
    )
    (net (code "94") (name "/VIN") (class "Default")
      (node (ref "U1") (pin "VIN") (pinfunction "VIN_VIN") (pintype "bidirectional"))
    )
    (net (code "95") (name "/X-MAX") (class "Default")
      (node (ref "U1") (pin "D17") (pinfunction "D17_D17") (pintype "bidirectional"))
      (node (ref "X-MAX") (pin "3") (pinfunction "3_3") (pintype "passive"))
    )
    (net (code "96") (name "/X-MIN") (class "Default")
      (node (ref "U1") (pin "D16") (pinfunction "D16_D16") (pintype "bidirectional"))
      (node (ref "X-MIN") (pin "3") (pinfunction "3_3") (pintype "passive"))
    )
    (net (code "97") (name "/Y-MAX") (class "Default")
      (node (ref "U1") (pin "D15") (pinfunction "D15_D15") (pintype "bidirectional"))
      (node (ref "Y-MAX") (pin "3") (pinfunction "3_3") (pintype "passive"))
    )
    (net (code "98") (name "/Y-MIN") (class "Default")
      (node (ref "U1") (pin "D14") (pinfunction "D14_D14") (pintype "bidirectional"))
      (node (ref "Y-MIN") (pin "3") (pinfunction "3_3") (pintype "passive"))
    )
    (net (code "99") (name "GND") (class "Default")
      (node (ref "A_STP") (pin "C") (pinfunction "C_C") (pintype "passive"))
      (node (ref "B_STP") (pin "C") (pinfunction "C_C") (pintype "passive"))
      (node (ref "C1") (pin "-") (pinfunction "-_-") (pintype "passive"))
      (node (ref "C10") (pin "1") (pinfunction "1_1") (pintype "passive"))
      (node (ref "C11") (pin "-") (pinfunction "-_-") (pintype "passive"))
      (node (ref "C12") (pin "-") (pinfunction "-_-") (pintype "passive"))
      (node (ref "C13") (pin "1") (pinfunction "1_1") (pintype "passive"))
      (node (ref "C14") (pin "1") (pinfunction "1_1") (pintype "passive"))
      (node (ref "C3") (pin "-") (pinfunction "-_-") (pintype "passive"))
      (node (ref "C4") (pin "-") (pinfunction "-_-") (pintype "passive"))
      (node (ref "C6") (pin "1") (pinfunction "1_1") (pintype "passive"))
      (node (ref "C7") (pin "2") (pinfunction "2_2") (pintype "passive"))
      (node (ref "C9") (pin "2") (pinfunction "2_2") (pintype "passive"))
      (node (ref "C_STP") (pin "C") (pinfunction "C_C") (pintype "passive"))
      (node (ref "D13") (pin "C") (pinfunction "C_C") (pintype "passive"))
      (node (ref "IC1") (pin "GND") (pinfunction "GND_GND") (pintype "bidirectional"))
      (node (ref "IC1") (pin "GND1") (pinfunction "GND1_GND1") (pintype "bidirectional"))
      (node (ref "IC2") (pin "1") (pinfunction "G1_1") (pintype "input"))
      (node (ref "IC2") (pin "10") (pinfunction "GND_10") (pintype "power_in"))
      (node (ref "IC2") (pin "19") (pinfunction "G2_19") (pintype "input"))
      (node (ref "IC3") (pin "1") (pinfunction "G1_1") (pintype "input"))
      (node (ref "IC3") (pin "10") (pinfunction "GND_10") (pintype "power_in"))
      (node (ref "IC3") (pin "19") (pinfunction "G2_19") (pintype "input"))
      (node (ref "IC3") (pin "4") (pinfunction "A3_4") (pintype "input"))
      (node (ref "IC3") (pin "5") (pinfunction "A4_5") (pintype "input"))
      (node (ref "IC3") (pin "6") (pinfunction "A5_6") (pintype "input"))
      (node (ref "IC3") (pin "7") (pinfunction "A6_7") (pintype "input"))
      (node (ref "IC3") (pin "9") (pinfunction "A8_9") (pintype "input"))
      (node (ref "IC4") (pin "1") (pinfunction "G1_1") (pintype "input"))
      (node (ref "IC4") (pin "10") (pinfunction "GND_10") (pintype "power_in"))
      (node (ref "IC4") (pin "19") (pinfunction "G2_19") (pintype "input"))
      (node (ref "IC4") (pin "9") (pinfunction "A8_9") (pintype "input"))
      (node (ref "IC5") (pin "1") (pinfunction "G1_1") (pintype "input"))
      (node (ref "IC5") (pin "10") (pinfunction "GND_10") (pintype "power_in"))
      (node (ref "IC5") (pin "19") (pinfunction "G2_19") (pintype "input"))
      (node (ref "IC5") (pin "2") (pinfunction "A1_2") (pintype "input"))
      (node (ref "IC5") (pin "6") (pinfunction "A5_6") (pintype "input"))
      (node (ref "IC5") (pin "7") (pinfunction "A6_7") (pintype "input"))
      (node (ref "IC5") (pin "8") (pinfunction "A7_8") (pintype "input"))
      (node (ref "IC5") (pin "9") (pinfunction "A8_9") (pintype "input"))
      (node (ref "J1") (pin "2") (pinfunction "2_2") (pintype "passive"))
      (node (ref "JP8") (pin "GND") (pinfunction "GND_GND") (pintype "bidirectional"))
      (node (ref "JP8") (pin "GNDBREAK") (pinfunction "GNDBREAK_GNDBREAK") (pintype "bidirectional"))
      (node (ref "PWR") (pin "C") (pinfunction "C_C") (pintype "passive"))
      (node (ref "PWR1") (pin "C") (pinfunction "C_C") (pintype "passive"))
      (node (ref "R1") (pin "2") (pinfunction "2_2") (pintype "passive"))
      (node (ref "R10") (pin "1") (pinfunction "1_1") (pintype "passive"))
      (node (ref "R11") (pin "1") (pinfunction "1_1") (pintype "passive"))
      (node (ref "R5") (pin "2") (pinfunction "2_2") (pintype "passive"))
      (node (ref "R7") (pin "1") (pinfunction "1_1") (pintype "passive"))
      (node (ref "S2") (pin "1") (pinfunction "1_1") (pintype "passive"))
      (node (ref "S2") (pin "2") (pinfunction "2_2") (pintype "passive"))
      (node (ref "SER1") (pin "1") (pinfunction "1_1") (pintype "passive"))
      (node (ref "SER2") (pin "1") (pinfunction "1_1") (pintype "passive"))
      (node (ref "TFT") (pin "1") (pinfunction "1_1") (pintype "passive"))
      (node (ref "TFT") (pin "10") (pinfunction "10_10") (pintype "passive"))
      (node (ref "TFT") (pin "12") (pinfunction "12_12") (pintype "passive"))
      (node (ref "TFT") (pin "14") (pinfunction "14_14") (pintype "passive"))
      (node (ref "TFT") (pin "16") (pinfunction "16_16") (pintype "passive"))
      (node (ref "TFT") (pin "2") (pinfunction "2_2") (pintype "passive"))
      (node (ref "TFT") (pin "4") (pinfunction "4_4") (pintype "passive"))
      (node (ref "TFT") (pin "6") (pinfunction "6_6") (pintype "passive"))
      (node (ref "TFT") (pin "8") (pinfunction "8_8") (pintype "passive"))
      (node (ref "U$1") (pin "GND") (pinfunction "GND_GND") (pintype "power_in"))
      (node (ref "U$1") (pin "GND@0") (pinfunction "GND_GND@0") (pintype "power_in"))
      (node (ref "U$6") (pin "GND") (pinfunction "GND_GND") (pintype "power_in"))
      (node (ref "U$6") (pin "GND@0") (pinfunction "GND_GND@0") (pintype "power_in"))
      (node (ref "U$7") (pin "GND") (pinfunction "GND_GND") (pintype "power_in"))
      (node (ref "U$7") (pin "GND@0") (pinfunction "GND_GND@0") (pintype "power_in"))
      (node (ref "U1") (pin "GND@0") (pinfunction "GND_GND@0") (pintype "power_in"))
      (node (ref "U1") (pin "GND@1") (pinfunction "GND_GND@1") (pintype "power_in"))
      (node (ref "U1") (pin "GND@2") (pinfunction "GND_GND@2") (pintype "power_in"))
      (node (ref "U1") (pin "GND@3") (pinfunction "GND_GND@3") (pintype "power_in"))
      (node (ref "U1") (pin "GND@4") (pinfunction "GND_GND@4") (pintype "power_in"))
      (node (ref "X-MAX") (pin "1") (pinfunction "1_1") (pintype "passive"))
      (node (ref "X-MIN") (pin "1") (pinfunction "1_1") (pintype "passive"))
      (node (ref "Y-MAX") (pin "1") (pinfunction "1_1") (pintype "passive"))
      (node (ref "Y-MIN") (pin "1") (pinfunction "1_1") (pintype "passive"))
    )
    (net (code "100") (name "Net-(A-MOT1-Pad1)") (class "Default")
      (node (ref "A-MOT1") (pin "1") (pinfunction "1_1") (pintype "bidirectional"))
      (node (ref "A-MOT2") (pin "1") (pinfunction "1_1") (pintype "passive"))
      (node (ref "U$1") (pin "2B") (pinfunction "2B_2B") (pintype "output"))
    )
    (net (code "101") (name "Net-(A-MOT1-Pad2)") (class "Default")
      (node (ref "A-MOT1") (pin "2") (pinfunction "2_2") (pintype "bidirectional"))
      (node (ref "A-MOT2") (pin "2") (pinfunction "2_2") (pintype "passive"))
      (node (ref "U$1") (pin "2A") (pinfunction "2A_2A") (pintype "output"))
    )
    (net (code "102") (name "Net-(A-MOT1-Pad3)") (class "Default")
      (node (ref "A-MOT1") (pin "3") (pinfunction "3_3") (pintype "bidirectional"))
      (node (ref "A-MOT2") (pin "3") (pinfunction "3_3") (pintype "passive"))
      (node (ref "U$1") (pin "1A") (pinfunction "1A_1A") (pintype "output"))
    )
    (net (code "103") (name "Net-(A-MOT1-Pad4)") (class "Default")
      (node (ref "A-MOT1") (pin "4") (pinfunction "4_4") (pintype "bidirectional"))
      (node (ref "A-MOT2") (pin "4") (pinfunction "4_4") (pintype "passive"))
      (node (ref "U$1") (pin "1B") (pinfunction "1B_1B") (pintype "output"))
    )
    (net (code "104") (name "Net-(A_STP-PadA)") (class "Default")
      (node (ref "A_STP") (pin "A") (pinfunction "A_A") (pintype "passive"))
      (node (ref "R6") (pin "2") (pinfunction "2_2") (pintype "passive"))
    )
    (net (code "105") (name "Net-(B-MOT1-Pad1)") (class "Default")
      (node (ref "B-MOT1") (pin "1") (pinfunction "1_1") (pintype "bidirectional"))
      (node (ref "B-MOT2") (pin "1") (pinfunction "1_1") (pintype "passive"))
      (node (ref "U$7") (pin "2B") (pinfunction "2B_2B") (pintype "output"))
    )
    (net (code "106") (name "Net-(B-MOT1-Pad2)") (class "Default")
      (node (ref "B-MOT1") (pin "2") (pinfunction "2_2") (pintype "bidirectional"))
      (node (ref "B-MOT2") (pin "2") (pinfunction "2_2") (pintype "passive"))
      (node (ref "U$7") (pin "2A") (pinfunction "2A_2A") (pintype "output"))
    )
    (net (code "107") (name "Net-(B-MOT1-Pad3)") (class "Default")
      (node (ref "B-MOT1") (pin "3") (pinfunction "3_3") (pintype "bidirectional"))
      (node (ref "B-MOT2") (pin "3") (pinfunction "3_3") (pintype "passive"))
      (node (ref "U$7") (pin "1A") (pinfunction "1A_1A") (pintype "output"))
    )
    (net (code "108") (name "Net-(B-MOT1-Pad4)") (class "Default")
      (node (ref "B-MOT1") (pin "4") (pinfunction "4_4") (pintype "bidirectional"))
      (node (ref "B-MOT2") (pin "4") (pinfunction "4_4") (pintype "passive"))
      (node (ref "U$7") (pin "1B") (pinfunction "1B_1B") (pintype "output"))
    )
    (net (code "109") (name "Net-(B_STP-PadA)") (class "Default")
      (node (ref "B_STP") (pin "A") (pinfunction "A_A") (pintype "passive"))
      (node (ref "R8") (pin "2") (pinfunction "2_2") (pintype "passive"))
    )
    (net (code "110") (name "Net-(C-MOT1-Pad1)") (class "Default")
      (node (ref "C-MOT1") (pin "1") (pinfunction "1_1") (pintype "bidirectional"))
      (node (ref "C-MOT2") (pin "1") (pinfunction "1_1") (pintype "passive"))
      (node (ref "U$6") (pin "2B") (pinfunction "2B_2B") (pintype "output"))
    )
    (net (code "111") (name "Net-(C-MOT1-Pad2)") (class "Default")
      (node (ref "C-MOT1") (pin "2") (pinfunction "2_2") (pintype "bidirectional"))
      (node (ref "C-MOT2") (pin "2") (pinfunction "2_2") (pintype "passive"))
      (node (ref "U$6") (pin "2A") (pinfunction "2A_2A") (pintype "output"))
    )
    (net (code "112") (name "Net-(C-MOT1-Pad3)") (class "Default")
      (node (ref "C-MOT1") (pin "3") (pinfunction "3_3") (pintype "bidirectional"))
      (node (ref "C-MOT2") (pin "3") (pinfunction "3_3") (pintype "passive"))
      (node (ref "U$6") (pin "1A") (pinfunction "1A_1A") (pintype "output"))
    )
    (net (code "113") (name "Net-(C-MOT1-Pad4)") (class "Default")
      (node (ref "C-MOT1") (pin "4") (pinfunction "4_4") (pintype "bidirectional"))
      (node (ref "C-MOT2") (pin "4") (pinfunction "4_4") (pintype "passive"))
      (node (ref "U$6") (pin "1B") (pinfunction "1B_1B") (pintype "output"))
    )
    (net (code "114") (name "Net-(C5-Pad1)") (class "Default")
      (node (ref "C5") (pin "1") (pinfunction "1_1") (pintype "passive"))
      (node (ref "IC1") (pin "COMP") (pinfunction "COMP_COMP") (pintype "bidirectional"))
    )
    (net (code "115") (name "Net-(C5-Pad2)") (class "Default")
      (node (ref "C5") (pin "2") (pinfunction "2_2") (pintype "passive"))
      (node (ref "R7") (pin "2") (pinfunction "2_2") (pintype "passive"))
    )
    (net (code "116") (name "Net-(C8-Pad1)") (class "Default")
      (node (ref "C8") (pin "1") (pinfunction "1_1") (pintype "passive"))
      (node (ref "IC1") (pin "BS") (pinfunction "BS_BS") (pintype "bidirectional"))
    )
    (net (code "117") (name "Net-(C8-Pad2)") (class "Default")
      (node (ref "C8") (pin "2") (pinfunction "2_2") (pintype "passive"))
      (node (ref "IC1") (pin "SW") (pinfunction "SW_SW") (pintype "bidirectional"))
      (node (ref "L1") (pin "1") (pinfunction "1_1") (pintype "passive"))
    )
    (net (code "118") (name "Net-(C9-Pad1)") (class "Default")
      (node (ref "C9") (pin "1") (pinfunction "1_1") (pintype "passive"))
      (node (ref "IC1") (pin "SS") (pinfunction "SS_SS") (pintype "bidirectional"))
    )
    (net (code "119") (name "Net-(C12-Pad+)") (class "Default")
      (node (ref "C12") (pin "+") (pinfunction "+_+") (pintype "passive"))
      (node (ref "C7") (pin "1") (pinfunction "1_1") (pintype "passive"))
      (node (ref "D2") (pin "A") (pinfunction "A_A") (pintype "passive"))
      (node (ref "L1") (pin "2") (pinfunction "2_2") (pintype "passive"))
      (node (ref "ON_BOARD_PWR") (pin "1") (pinfunction "1_1") (pintype "passive"))
      (node (ref "ON_BOARD_PWR") (pin "2") (pinfunction "2_2") (pintype "passive"))
      (node (ref "R12") (pin "1") (pinfunction "1_1") (pintype "passive"))
      (node (ref "R9") (pin "2") (pinfunction "2_2") (pintype "passive"))
    )
    (net (code "120") (name "Net-(C_STP-PadA)") (class "Default")
      (node (ref "C_STP") (pin "A") (pinfunction "A_A") (pintype "passive"))
      (node (ref "R3") (pin "1") (pinfunction "1_1") (pintype "passive"))
    )
    (net (code "121") (name "Net-(D13-PadA)") (class "Default")
      (node (ref "D13") (pin "A") (pinfunction "A_A") (pintype "passive"))
      (node (ref "R14") (pin "2") (pinfunction "2_2") (pintype "passive"))
    )
    (net (code "122") (name "Net-(IC1-PadEN)") (class "Default")
      (node (ref "IC1") (pin "EN") (pinfunction "EN_EN") (pintype "bidirectional"))
      (node (ref "R4") (pin "2") (pinfunction "2_2") (pintype "passive"))
    )
    (net (code "123") (name "Net-(IC1-PadFB)") (class "Default")
      (node (ref "IC1") (pin "FB") (pinfunction "FB_FB") (pintype "bidirectional"))
      (node (ref "R10") (pin "2") (pinfunction "2_2") (pintype "passive"))
      (node (ref "R9") (pin "1") (pinfunction "1_1") (pintype "passive"))
    )
    (net (code "124") (name "Net-(PWR-PadA)") (class "Default")
      (node (ref "PWR") (pin "A") (pinfunction "A_A") (pintype "passive"))
      (node (ref "R17") (pin "2") (pinfunction "2_2") (pintype "passive"))
    )
    (net (code "125") (name "Net-(PWR1-PadA)") (class "Default")
      (node (ref "PWR1") (pin "A") (pinfunction "A_A") (pintype "passive"))
      (node (ref "R12") (pin "2") (pinfunction "2_2") (pintype "passive"))
    )
    (net (code "126") (name "Net-(R1-Pad1)") (class "Default")
      (node (ref "R1") (pin "1") (pinfunction "1_1") (pintype "passive"))
      (node (ref "SJ7") (pin "2") (pinfunction "2_2") (pintype "passive"))
      (node (ref "U$1") (pin "MS1") (pinfunction "MS1_MS1") (pintype "input"))
    )
    (net (code "127") (name "Net-(R5-Pad1)") (class "Default")
      (node (ref "R5") (pin "1") (pinfunction "1_1") (pintype "passive"))
      (node (ref "SJ1") (pin "2") (pinfunction "2_2") (pintype "passive"))
      (node (ref "U$6") (pin "MS1") (pinfunction "MS1_MS1") (pintype "input"))
    )
    (net (code "128") (name "Net-(R11-Pad2)") (class "Default")
      (node (ref "R11") (pin "2") (pinfunction "2_2") (pintype "passive"))
      (node (ref "SJ3") (pin "2") (pinfunction "2_2") (pintype "passive"))
      (node (ref "U$7") (pin "MS1") (pinfunction "MS1_MS1") (pintype "input"))
    )
    (net (code "129") (name "Net-(R15-Pad2)") (class "Default")
      (node (ref "R15") (pin "2") (pinfunction "2_2") (pintype "passive"))
      (node (ref "TX_LED") (pin "C") (pinfunction "C_C") (pintype "passive"))
    )
    (net (code "130") (name "Net-(R16-Pad2)") (class "Default")
      (node (ref "R16") (pin "2") (pinfunction "2_2") (pintype "passive"))
      (node (ref "RX_LED") (pin "C") (pinfunction "C_C") (pintype "passive"))
    )
    (net (code "131") (name "Net-(SJ2-Pad2)") (class "Default")
      (node (ref "SJ2") (pin "2") (pinfunction "2_2") (pintype "passive"))
      (node (ref "U$6") (pin "MS2") (pinfunction "MS2_MS2") (pintype "input"))
    )
    (net (code "132") (name "Net-(SJ4-Pad2)") (class "Default")
      (node (ref "SJ4") (pin "2") (pinfunction "2_2") (pintype "passive"))
      (node (ref "U$7") (pin "MS2") (pinfunction "MS2_MS2") (pintype "input"))
    )
    (net (code "133") (name "Net-(SJ5-Pad2)") (class "Default")
      (node (ref "SJ5") (pin "2") (pinfunction "2_2") (pintype "passive"))
      (node (ref "U$6") (pin "MS3") (pinfunction "MS3_MS3") (pintype "input"))
    )
    (net (code "134") (name "Net-(SJ6-Pad2)") (class "Default")
      (node (ref "SJ6") (pin "2") (pinfunction "2_2") (pintype "passive"))
      (node (ref "U$7") (pin "MS3") (pinfunction "MS3_MS3") (pintype "input"))
    )
    (net (code "135") (name "Net-(SJ8-Pad2)") (class "Default")
      (node (ref "SJ8") (pin "2") (pinfunction "2_2") (pintype "passive"))
      (node (ref "U$1") (pin "MS2") (pinfunction "MS2_MS2") (pintype "input"))
    )
    (net (code "136") (name "Net-(SJ9-Pad2)") (class "Default")
      (node (ref "SJ9") (pin "2") (pinfunction "2_2") (pintype "passive"))
      (node (ref "U$1") (pin "MS3") (pinfunction "MS3_MS3") (pintype "input"))
    )
    (net (code "137") (name "Net-(U$1-SLEEP)") (class "Default")
      (node (ref "U$1") (pin "RST") (pinfunction "RST_RST") (pintype "input"))
      (node (ref "U$1") (pin "SLP") (pinfunction "SLEEP_SLP") (pintype "input"))
    )
    (net (code "138") (name "Net-(U$6-SLEEP)") (class "Default")
      (node (ref "U$6") (pin "RST") (pinfunction "RST_RST") (pintype "input"))
      (node (ref "U$6") (pin "SLP") (pinfunction "SLEEP_SLP") (pintype "input"))
    )
    (net (code "139") (name "Net-(U$7-SLEEP)") (class "Default")
      (node (ref "U$7") (pin "RST") (pinfunction "RST_RST") (pintype "input"))
      (node (ref "U$7") (pin "SLP") (pinfunction "SLEEP_SLP") (pintype "input"))
    )
    (net (code "140") (name "VCC") (class "Default")
      (node (ref "D2") (pin "C") (pinfunction "C_C") (pintype "passive"))
      (node (ref "IC5") (pin "20") (pinfunction "VCC_20") (pintype "power_in"))
      (node (ref "R17") (pin "1") (pinfunction "1_1") (pintype "passive"))
      (node (ref "R18") (pin "1") (pinfunction "1_1") (pintype "passive"))
      (node (ref "R19") (pin "1") (pinfunction "1_1") (pintype "passive"))
      (node (ref "R2") (pin "1") (pinfunction "1_1") (pintype "passive"))
      (node (ref "RX_LED") (pin "A") (pinfunction "A_A") (pintype "passive"))
      (node (ref "SER1") (pin "2") (pinfunction "2_2") (pintype "passive"))
      (node (ref "SER2") (pin "2") (pinfunction "2_2") (pintype "passive"))
      (node (ref "SJ1") (pin "1") (pinfunction "1_1") (pintype "passive"))
      (node (ref "SJ2") (pin "1") (pinfunction "1_1") (pintype "passive"))
      (node (ref "SJ3") (pin "1") (pinfunction "1_1") (pintype "passive"))
      (node (ref "SJ4") (pin "1") (pinfunction "1_1") (pintype "passive"))
      (node (ref "SJ5") (pin "1") (pinfunction "1_1") (pintype "passive"))
      (node (ref "SJ6") (pin "1") (pinfunction "1_1") (pintype "passive"))
      (node (ref "SJ7") (pin "1") (pinfunction "1_1") (pintype "passive"))
      (node (ref "SJ8") (pin "1") (pinfunction "1_1") (pintype "passive"))
      (node (ref "SJ9") (pin "1") (pinfunction "1_1") (pintype "passive"))
      (node (ref "TFT") (pin "3") (pinfunction "3_3") (pintype "passive"))
      (node (ref "TX_LED") (pin "A") (pinfunction "A_A") (pintype "passive"))
      (node (ref "U$1") (pin "VDD") (pinfunction "VDD_VDD") (pintype "power_in"))
      (node (ref "U$6") (pin "VDD") (pinfunction "VDD_VDD") (pintype "power_in"))
      (node (ref "U$7") (pin "VDD") (pinfunction "VDD_VDD") (pintype "power_in"))
      (node (ref "U1") (pin "5V@0") (pinfunction "5V_5V@0") (pintype "power_in"))
      (node (ref "U1") (pin "5V@1") (pinfunction "5V_5V@1") (pintype "power_in"))
      (node (ref "U1") (pin "5V@2") (pinfunction "5V_5V@2") (pintype "power_in"))
      (node (ref "X-MAX") (pin "2") (pinfunction "2_2") (pintype "passive"))
      (node (ref "X-MIN") (pin "2") (pinfunction "2_2") (pintype "passive"))
      (node (ref "Y-MAX") (pin "2") (pinfunction "2_2") (pintype "passive"))
      (node (ref "Y-MIN") (pin "2") (pinfunction "2_2") (pintype "passive"))
    )
    (net (code "141") (name "unconnected-(IC3A-Y3-Pad16)") (class "Default")
      (node (ref "IC3") (pin "16") (pinfunction "Y3_16") (pintype "tri_state"))
    )
    (net (code "142") (name "unconnected-(IC3A-Y4-Pad15)") (class "Default")
      (node (ref "IC3") (pin "15") (pinfunction "Y4_15") (pintype "tri_state"))
    )
    (net (code "143") (name "unconnected-(IC3A-Y5-Pad14)") (class "Default")
      (node (ref "IC3") (pin "14") (pinfunction "Y5_14") (pintype "tri_state"))
    )
    (net (code "144") (name "unconnected-(IC3A-Y6-Pad13)") (class "Default")
      (node (ref "IC3") (pin "13") (pinfunction "Y6_13") (pintype "tri_state"))
    )
    (net (code "145") (name "unconnected-(IC3A-Y8-Pad11)") (class "Default")
      (node (ref "IC3") (pin "11") (pinfunction "Y8_11") (pintype "tri_state"))
    )
    (net (code "146") (name "unconnected-(IC4A-Y8-Pad11)") (class "Default")
      (node (ref "IC4") (pin "11") (pinfunction "Y8_11") (pintype "tri_state"))
    )
    (net (code "147") (name "unconnected-(IC5A-Y1-Pad18)") (class "Default")
      (node (ref "IC5") (pin "18") (pinfunction "Y1_18") (pintype "tri_state"))
    )
    (net (code "148") (name "unconnected-(IC5A-Y5-Pad14)") (class "Default")
      (node (ref "IC5") (pin "14") (pinfunction "Y5_14") (pintype "tri_state"))
    )
    (net (code "149") (name "unconnected-(IC5A-Y6-Pad13)") (class "Default")
      (node (ref "IC5") (pin "13") (pinfunction "Y6_13") (pintype "tri_state"))
    )
    (net (code "150") (name "unconnected-(IC5A-Y7-Pad12)") (class "Default")
      (node (ref "IC5") (pin "12") (pinfunction "Y7_12") (pintype "tri_state"))
    )
    (net (code "151") (name "unconnected-(IC5A-Y8-Pad11)") (class "Default")
      (node (ref "IC5") (pin "11") (pinfunction "Y8_11") (pintype "tri_state"))
    )
    (net (code "152") (name "unconnected-(TFT-Pad5)") (class "Default")
      (node (ref "TFT") (pin "5") (pinfunction "5_5") (pintype "passive"))
    )
    (net (code "153") (name "unconnected-(TFT-Pad24)") (class "Default")
      (node (ref "TFT") (pin "24") (pinfunction "24_24") (pintype "passive"))
    )
    (net (code "154") (name "unconnected-(TFT-Pad31)") (class "Default")
      (node (ref "TFT") (pin "31") (pinfunction "31_31") (pintype "passive"))
    )
    (net (code "155") (name "unconnected-(TFT-Pad35)") (class "Default")
      (node (ref "TFT") (pin "35") (pinfunction "35_35") (pintype "passive"))
    )
    (net (code "156") (name "unconnected-(TFT-Pad38)") (class "Default")
      (node (ref "TFT") (pin "38") (pinfunction "38_38") (pintype "passive"))
    )
    (net (code "157") (name "unconnected-(TFT-Pad39)") (class "Default")
      (node (ref "TFT") (pin "39") (pinfunction "39_39") (pintype "passive"))
    )
    (net (code "158") (name "unconnected-(TFT-Pad40)") (class "Default")
      (node (ref "TFT") (pin "40") (pinfunction "40_40") (pintype "passive"))
    )
  )
)
